# ADS1274.net
KiCad netlist of a schematic drawn in Altium Designer
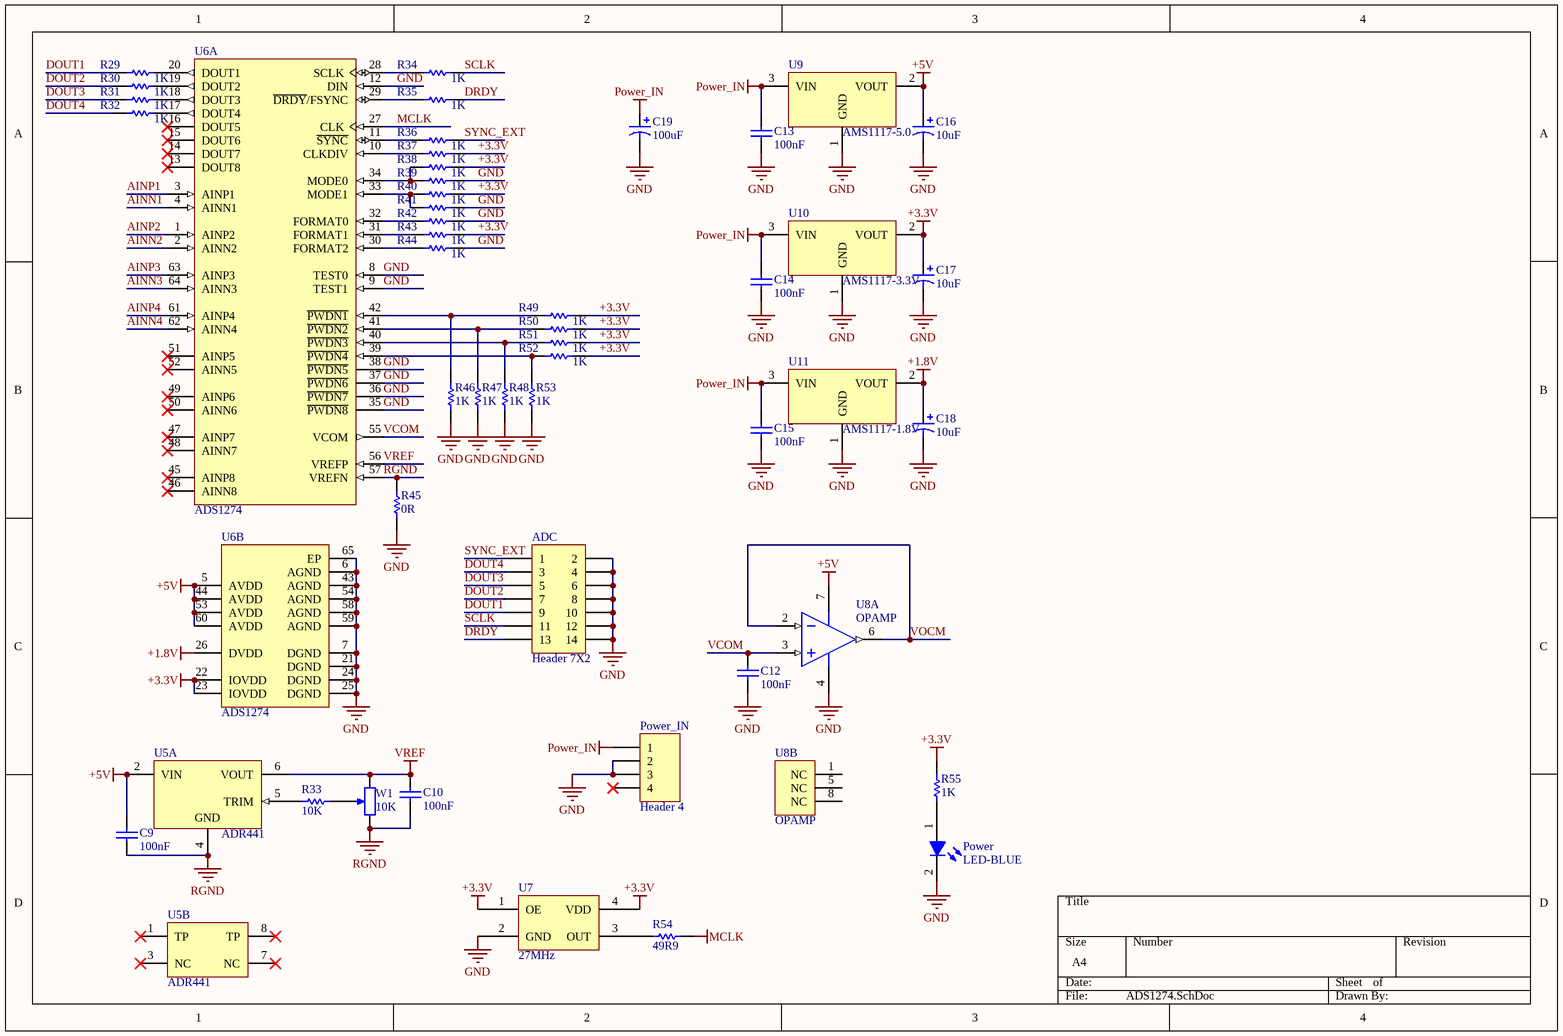
[diagram p0: ADS1274.SchDoc]

(export (version "E")
  (design (tool "Eeschema 10.0.6"))
  (components
    (comp (ref "ADC")
      (value "Header 7X2")
      (footprint "HEADER7X2")
      (description "Header, 7-Pin, Dual row")
      (fields (field (name "PUBLISHER") "Altium Limited"))
      (libsource (lib "Miscellaneous Connectors") (part "Header 7X2"))
    )
    (comp (ref "C9")
      (value "100nF")
      (footprint "CAPC0603(1608)55_M")
      (libsource (lib "Slivy's ibrary") (part "CAP"))
    )
    (comp (ref "C10")
      (value "100nF")
      (footprint "CAPC0603(1608)55_M")
      (libsource (lib "Slivy's ibrary") (part "CAP"))
    )
    (comp (ref "C12")
      (value "100nF")
      (footprint "CAPC0603(1608)55_M")
      (libsource (lib "Slivy's ibrary") (part "CAP"))
    )
    (comp (ref "C13")
      (value "100nF")
      (footprint "CAPC0603(1608)55_M")
      (libsource (lib "Slivy's ibrary") (part "CAP"))
    )
    (comp (ref "C14")
      (value "100nF")
      (footprint "CAPC0603(1608)55_M")
      (libsource (lib "Slivy's ibrary") (part "CAP"))
    )
    (comp (ref "C15")
      (value "100nF")
      (footprint "CAPC0603(1608)55_M")
      (libsource (lib "Slivy's ibrary") (part "CAP"))
    )
    (comp (ref "C16")
      (value "10uF")
      (footprint "CAPC3528")
      (libsource (lib "Slivy's ibrary") (part "CAP-Pol"))
    )
    (comp (ref "C17")
      (value "10uF")
      (footprint "CAPC3528")
      (libsource (lib "Slivy's ibrary") (part "CAP-Pol"))
    )
    (comp (ref "C18")
      (value "10uF")
      (footprint "CAPC3528")
      (libsource (lib "Slivy's ibrary") (part "CAP-Pol"))
    )
    (comp (ref "C19")
      (value "100uF")
      (footprint "CAPC7343")
      (libsource (lib "Slivy's ibrary") (part "CAP-Pol"))
    )
    (comp (ref "Power")
      (value "LED-BLUE")
      (footprint "0603LED_BLUE_V")
      (libsource (lib "Slivy's ibrary") (part "LED-BLUE"))
    )
    (comp (ref "Power_IN")
      (value "Header 4")
      (footprint "3.96-4")
      (description "Header, 4-Pin")
      (fields (field (name "PUBLISHER") "Altium Limited"))
      (libsource (lib "Miscellaneous Connectors") (part "Header 4"))
    )
    (comp (ref "R29")
      (value "1K")
      (footprint "RESC0603(1608)_M")
      (libsource (lib "Slivy's ibrary") (part "RES"))
    )
    (comp (ref "R30")
      (value "1K")
      (footprint "RESC0603(1608)_M")
      (libsource (lib "Slivy's ibrary") (part "RES"))
    )
    (comp (ref "R31")
      (value "1K")
      (footprint "RESC0603(1608)_M")
      (libsource (lib "Slivy's ibrary") (part "RES"))
    )
    (comp (ref "R32")
      (value "1K")
      (footprint "RESC0603(1608)_M")
      (libsource (lib "Slivy's ibrary") (part "RES"))
    )
    (comp (ref "R33")
      (value "10K")
      (footprint "RESC0603(1608)_M")
      (libsource (lib "Slivy's ibrary") (part "RES"))
    )
    (comp (ref "R34")
      (value "1K")
      (footprint "RESC0603(1608)_M")
      (libsource (lib "Slivy's ibrary") (part "RES"))
    )
    (comp (ref "R35")
      (value "1K")
      (footprint "RESC0603(1608)_M")
      (libsource (lib "Slivy's ibrary") (part "RES"))
    )
    (comp (ref "R36")
      (value "1K")
      (footprint "RESC0603(1608)_M")
      (libsource (lib "Slivy's ibrary") (part "RES"))
    )
    (comp (ref "R37")
      (value "1K")
      (footprint "RESC0603(1608)_M")
      (libsource (lib "Slivy's ibrary") (part "RES"))
    )
    (comp (ref "R38")
      (value "1K")
      (footprint "RESC0603(1608)_M")
      (libsource (lib "Slivy's ibrary") (part "RES"))
    )
    (comp (ref "R39")
      (value "1K")
      (footprint "RESC0603(1608)_M")
      (libsource (lib "Slivy's ibrary") (part "RES"))
    )
    (comp (ref "R40")
      (value "1K")
      (footprint "RESC0603(1608)_M")
      (libsource (lib "Slivy's ibrary") (part "RES"))
    )
    (comp (ref "R41")
      (value "1K")
      (footprint "RESC0603(1608)_M")
      (libsource (lib "Slivy's ibrary") (part "RES"))
    )
    (comp (ref "R42")
      (value "1K")
      (footprint "RESC0603(1608)_M")
      (libsource (lib "Slivy's ibrary") (part "RES"))
    )
    (comp (ref "R43")
      (value "1K")
      (footprint "RESC0603(1608)_M")
      (libsource (lib "Slivy's ibrary") (part "RES"))
    )
    (comp (ref "R44")
      (value "1K")
      (footprint "RESC0603(1608)_M")
      (libsource (lib "Slivy's ibrary") (part "RES"))
    )
    (comp (ref "R45")
      (value "0R")
      (footprint "RESC0603(1608)_M")
      (libsource (lib "Slivy's ibrary") (part "RES"))
    )
    (comp (ref "R46")
      (value "1K")
      (footprint "RESC0603(1608)_M")
      (libsource (lib "Slivy's ibrary") (part "RES"))
    )
    (comp (ref "R47")
      (value "1K")
      (footprint "RESC0603(1608)_M")
      (libsource (lib "Slivy's ibrary") (part "RES"))
    )
    (comp (ref "R48")
      (value "1K")
      (footprint "RESC0603(1608)_M")
      (libsource (lib "Slivy's ibrary") (part "RES"))
    )
    (comp (ref "R49")
      (value "1K")
      (footprint "RESC0603(1608)_M")
      (libsource (lib "Slivy's ibrary") (part "RES"))
    )
    (comp (ref "R50")
      (value "1K")
      (footprint "RESC0603(1608)_M")
      (libsource (lib "Slivy's ibrary") (part "RES"))
    )
    (comp (ref "R51")
      (value "1K")
      (footprint "RESC0603(1608)_M")
      (libsource (lib "Slivy's ibrary") (part "RES"))
    )
    (comp (ref "R52")
      (value "1K")
      (footprint "RESC0603(1608)_M")
      (libsource (lib "Slivy's ibrary") (part "RES"))
    )
    (comp (ref "R53")
      (value "1K")
      (footprint "RESC0603(1608)_M")
      (libsource (lib "Slivy's ibrary") (part "RES"))
    )
    (comp (ref "R54")
      (value "49R9")
      (footprint "RESC0603(1608)_M")
      (libsource (lib "Slivy's ibrary") (part "RES"))
    )
    (comp (ref "R55")
      (value "1K")
      (footprint "RESC0603(1608)_M")
      (libsource (lib "Slivy's ibrary") (part "RES"))
    )
    (comp (ref "U5") (value "ADR441") (footprint "SOIC8") (libsource (lib "Slivy's ibrary") (part "ADR421")))
    (comp (ref "U6") (value "ADS1274") (footprint "EQFP64") (libsource (lib "") (part "ADS1274_1")))
    (comp (ref "U7")
      (value "27MHz")
      (footprint "SMD7050")
      (libsource (lib "Integrated_Library1") (part "OSC7050"))
    )
    (comp (ref "U8") (value "OPAMP") (footprint "SOIC8") (libsource (lib "Slivy's ibrary") (part "OPAMP")))
    (comp (ref "U9")
      (value "AMS1117-5.0")
      (footprint "SOT-223_M")
      (libsource (lib "Slivy's ibrary") (part "AMS1117"))
    )
    (comp (ref "U10")
      (value "AMS1117-3.3V")
      (footprint "SOT-223_M")
      (libsource (lib "Slivy's ibrary") (part "AMS1117"))
    )
    (comp (ref "U11")
      (value "AMS1117-1.8V")
      (footprint "SOT-223_M")
      (libsource (lib "Slivy's ibrary") (part "AMS1117"))
    )
    (comp (ref "W1")
      (value "10K")
      (footprint "VR5")
      (description "Potentiometer")
      (fields
        (field (name "MANUFACTURER") "Generic Components")
        (field (name "PUBLISHER") "Altium Hobart Technology Centre")
      )
      (libsource (lib "Integrated_Library1") (part "RPot2"))
    )
  )
  (nets
    (net (code "1") (name "+1.8V") (class "Default")
      (node (ref "C18") (pin "1") (pinfunction "1_1") (pintype "passive"))
      (node (ref "U11") (pin "2") (pinfunction "VOUT_2") (pintype "power_in"))
      (node (ref "U6") (pin "26") (pinfunction "DVDD_26") (pintype "power_in"))
    )
    (net (code "2") (name "+3.3V") (class "Default")
      (node (ref "C17") (pin "1") (pinfunction "1_1") (pintype "passive"))
      (node (ref "R37") (pin "2") (pinfunction "2_2") (pintype "passive"))
      (node (ref "R38") (pin "2") (pinfunction "2_2") (pintype "passive"))
      (node (ref "R40") (pin "2") (pinfunction "2_2") (pintype "passive"))
      (node (ref "R43") (pin "2") (pinfunction "2_2") (pintype "passive"))
      (node (ref "R49") (pin "2") (pinfunction "2_2") (pintype "passive"))
      (node (ref "R50") (pin "2") (pinfunction "2_2") (pintype "passive"))
      (node (ref "R51") (pin "2") (pinfunction "2_2") (pintype "passive"))
      (node (ref "R52") (pin "2") (pinfunction "2_2") (pintype "passive"))
      (node (ref "R55") (pin "2") (pinfunction "2_2") (pintype "passive"))
      (node (ref "U10") (pin "2") (pinfunction "VOUT_2") (pintype "power_in"))
      (node (ref "U6") (pin "22") (pinfunction "IOVDD_22") (pintype "power_in"))
      (node (ref "U6") (pin "23") (pinfunction "IOVDD_23") (pintype "power_in"))
      (node (ref "U7") (pin "1") (pinfunction "OE_1") (pintype "passive"))
      (node (ref "U7") (pin "4") (pinfunction "VDD_4") (pintype "passive"))
    )
    (net (code "3") (name "+5V") (class "Default")
      (node (ref "C16") (pin "1") (pinfunction "1_1") (pintype "passive"))
      (node (ref "C9") (pin "2") (pinfunction "2_2") (pintype "passive"))
      (node (ref "U5") (pin "2") (pinfunction "VIN_2") (pintype "power_in"))
      (node (ref "U6") (pin "44") (pinfunction "AVDD_44") (pintype "power_in"))
      (node (ref "U6") (pin "5") (pinfunction "AVDD_5") (pintype "power_in"))
      (node (ref "U6") (pin "53") (pinfunction "AVDD_53") (pintype "power_in"))
      (node (ref "U6") (pin "60") (pinfunction "AVDD_60") (pintype "power_in"))
      (node (ref "U8") (pin "7") (pinfunction "V+_7") (pintype "power_in"))
      (node (ref "U9") (pin "2") (pinfunction "VOUT_2") (pintype "power_in"))
    )
    (net (code "4") (name "/AINN1") (class "Default")
      (node (ref "U6") (pin "4") (pinfunction "AINN1_4") (pintype "input"))
    )
    (net (code "5") (name "/AINN2") (class "Default")
      (node (ref "U6") (pin "2") (pinfunction "AINN2_2") (pintype "input"))
    )
    (net (code "6") (name "/AINN3") (class "Default")
      (node (ref "U6") (pin "64") (pinfunction "AINN3_64") (pintype "input"))
    )
    (net (code "7") (name "/AINN4") (class "Default")
      (node (ref "U6") (pin "62") (pinfunction "AINN4_62") (pintype "input"))
    )
    (net (code "8") (name "/AINP1") (class "Default")
      (node (ref "U6") (pin "3") (pinfunction "AINP1_3") (pintype "input"))
    )
    (net (code "9") (name "/AINP2") (class "Default")
      (node (ref "U6") (pin "1") (pinfunction "AINP2_1") (pintype "input"))
    )
    (net (code "10") (name "/AINP3") (class "Default")
      (node (ref "U6") (pin "63") (pinfunction "AINP3_63") (pintype "input"))
    )
    (net (code "11") (name "/AINP4") (class "Default")
      (node (ref "U6") (pin "61") (pinfunction "AINP4_61") (pintype "input"))
    )
    (net (code "12") (name "/DOUT1") (class "Default")
      (node (ref "ADC") (pin "9") (pinfunction "9_9") (pintype "passive"))
      (node (ref "R29") (pin "1") (pinfunction "1_1") (pintype "passive"))
    )
    (net (code "13") (name "/DOUT2") (class "Default")
      (node (ref "ADC") (pin "7") (pinfunction "7_7") (pintype "passive"))
      (node (ref "R30") (pin "1") (pinfunction "1_1") (pintype "passive"))
    )
    (net (code "14") (name "/DOUT3") (class "Default")
      (node (ref "ADC") (pin "5") (pinfunction "5_5") (pintype "passive"))
      (node (ref "R31") (pin "1") (pinfunction "1_1") (pintype "passive"))
    )
    (net (code "15") (name "/DOUT4") (class "Default")
      (node (ref "ADC") (pin "3") (pinfunction "3_3") (pintype "passive"))
      (node (ref "R32") (pin "1") (pinfunction "1_1") (pintype "passive"))
    )
    (net (code "16") (name "/DRDY") (class "Default")
      (node (ref "ADC") (pin "13") (pinfunction "13_13") (pintype "passive"))
      (node (ref "R35") (pin "2") (pinfunction "2_2") (pintype "passive"))
    )
    (net (code "17") (name "/SCLK") (class "Default")
      (node (ref "ADC") (pin "11") (pinfunction "11_11") (pintype "passive"))
      (node (ref "R34") (pin "2") (pinfunction "2_2") (pintype "passive"))
    )
    (net (code "18") (name "/SYNC_EXT") (class "Default")
      (node (ref "ADC") (pin "1") (pinfunction "1_1") (pintype "passive"))
      (node (ref "R36") (pin "2") (pinfunction "2_2") (pintype "passive"))
    )
    (net (code "19") (name "/VCOM") (class "Default")
      (node (ref "C12") (pin "2") (pinfunction "2_2") (pintype "passive"))
      (node (ref "U6") (pin "55") (pinfunction "VCOM_55") (pintype "output"))
      (node (ref "U8") (pin "3") (pinfunction "IN+_3") (pintype "input"))
    )
    (net (code "20") (name "/VOCM") (class "Default")
      (node (ref "U8") (pin "2") (pinfunction "IN-_2") (pintype "input"))
      (node (ref "U8") (pin "6") (pinfunction "OUT_6") (pintype "output"))
    )
    (net (code "21") (name "GND") (class "Default")
      (node (ref "ADC") (pin "10") (pinfunction "10_10") (pintype "passive"))
      (node (ref "ADC") (pin "12") (pinfunction "12_12") (pintype "passive"))
      (node (ref "ADC") (pin "14") (pinfunction "14_14") (pintype "passive"))
      (node (ref "ADC") (pin "2") (pinfunction "2_2") (pintype "passive"))
      (node (ref "ADC") (pin "4") (pinfunction "4_4") (pintype "passive"))
      (node (ref "ADC") (pin "6") (pinfunction "6_6") (pintype "passive"))
      (node (ref "ADC") (pin "8") (pinfunction "8_8") (pintype "passive"))
      (node (ref "C12") (pin "1") (pinfunction "1_1") (pintype "passive"))
      (node (ref "C13") (pin "1") (pinfunction "1_1") (pintype "passive"))
      (node (ref "C14") (pin "1") (pinfunction "1_1") (pintype "passive"))
      (node (ref "C15") (pin "1") (pinfunction "1_1") (pintype "passive"))
      (node (ref "C16") (pin "2") (pinfunction "2_2") (pintype "passive"))
      (node (ref "C17") (pin "2") (pinfunction "2_2") (pintype "passive"))
      (node (ref "C18") (pin "2") (pinfunction "2_2") (pintype "passive"))
      (node (ref "C19") (pin "2") (pinfunction "2_2") (pintype "passive"))
      (node (ref "Power") (pin "2") (pinfunction "K_2") (pintype "passive"))
      (node (ref "Power_IN") (pin "2") (pinfunction "2_2") (pintype "passive"))
      (node (ref "Power_IN") (pin "3") (pinfunction "3_3") (pintype "passive"))
      (node (ref "R39") (pin "2") (pinfunction "2_2") (pintype "passive"))
      (node (ref "R41") (pin "2") (pinfunction "2_2") (pintype "passive"))
      (node (ref "R42") (pin "2") (pinfunction "2_2") (pintype "passive"))
      (node (ref "R44") (pin "2") (pinfunction "2_2") (pintype "passive"))
      (node (ref "R45") (pin "1") (pinfunction "1_1") (pintype "passive"))
      (node (ref "R46") (pin "1") (pinfunction "1_1") (pintype "passive"))
      (node (ref "R47") (pin "1") (pinfunction "1_1") (pintype "passive"))
      (node (ref "R48") (pin "1") (pinfunction "1_1") (pintype "passive"))
      (node (ref "R53") (pin "1") (pinfunction "1_1") (pintype "passive"))
      (node (ref "U10") (pin "1") (pinfunction "GND_1") (pintype "power_in"))
      (node (ref "U11") (pin "1") (pinfunction "GND_1") (pintype "power_in"))
      (node (ref "U6") (pin "12") (pinfunction "DIN_12") (pintype "input"))
      (node (ref "U6") (pin "21") (pinfunction "DGND_21") (pintype "power_in"))
      (node (ref "U6") (pin "24") (pinfunction "DGND_24") (pintype "power_in"))
      (node (ref "U6") (pin "25") (pinfunction "DGND_25") (pintype "power_in"))
      (node (ref "U6") (pin "35") (pinfunction "~{PWDN8}_35") (pintype "passive"))
      (node (ref "U6") (pin "36") (pinfunction "~{PWDN7}_36") (pintype "passive"))
      (node (ref "U6") (pin "37") (pinfunction "~{PWDN6}_37") (pintype "passive"))
      (node (ref "U6") (pin "38") (pinfunction "~{PWDN5}_38") (pintype "passive"))
      (node (ref "U6") (pin "43") (pinfunction "AGND_43") (pintype "power_in"))
      (node (ref "U6") (pin "54") (pinfunction "AGND_54") (pintype "power_in"))
      (node (ref "U6") (pin "58") (pinfunction "AGND_58") (pintype "power_in"))
      (node (ref "U6") (pin "59") (pinfunction "AGND_59") (pintype "power_in"))
      (node (ref "U6") (pin "6") (pinfunction "AGND_6") (pintype "power_in"))
      (node (ref "U6") (pin "65") (pinfunction "EP_65") (pintype "passive"))
      (node (ref "U6") (pin "7") (pinfunction "DGND_7") (pintype "power_in"))
      (node (ref "U6") (pin "8") (pinfunction "TEST0_8") (pintype "input"))
      (node (ref "U6") (pin "9") (pinfunction "TEST1_9") (pintype "input"))
      (node (ref "U7") (pin "2") (pinfunction "GND_2") (pintype "passive"))
      (node (ref "U8") (pin "4") (pinfunction "V-_4") (pintype "power_in"))
      (node (ref "U9") (pin "1") (pinfunction "GND_1") (pintype "power_in"))
    )
    (net (code "22") (name "MCLK") (class "Default")
      (node (ref "R54") (pin "2") (pinfunction "2_2") (pintype "passive"))
      (node (ref "U6") (pin "27") (pinfunction "CLK_27") (pintype "input"))
    )
    (net (code "23") (name "Net-(Power-A)") (class "Default")
      (node (ref "Power") (pin "1") (pinfunction "A_1") (pintype "passive"))
      (node (ref "R55") (pin "1") (pinfunction "1_1") (pintype "passive"))
    )
    (net (code "24") (name "Net-(U5A-TRIM)") (class "Default")
      (node (ref "R33") (pin "1") (pinfunction "1_1") (pintype "passive"))
      (node (ref "U5") (pin "5") (pinfunction "TRIM_5") (pintype "input"))
    )
    (net (code "25") (name "Net-(U6A-CLKDIV)") (class "Default")
      (node (ref "R37") (pin "1") (pinfunction "1_1") (pintype "passive"))
      (node (ref "U6") (pin "10") (pinfunction "CLKDIV_10") (pintype "input"))
    )
    (net (code "26") (name "Net-(U6A-DOUT1)") (class "Default")
      (node (ref "R29") (pin "2") (pinfunction "2_2") (pintype "passive"))
      (node (ref "U6") (pin "20") (pinfunction "DOUT1_20") (pintype "output"))
    )
    (net (code "27") (name "Net-(U6A-DOUT2)") (class "Default")
      (node (ref "R30") (pin "2") (pinfunction "2_2") (pintype "passive"))
      (node (ref "U6") (pin "19") (pinfunction "DOUT2_19") (pintype "output"))
    )
    (net (code "28") (name "Net-(U6A-DOUT3)") (class "Default")
      (node (ref "R31") (pin "2") (pinfunction "2_2") (pintype "passive"))
      (node (ref "U6") (pin "18") (pinfunction "DOUT3_18") (pintype "output"))
    )
    (net (code "29") (name "Net-(U6A-DOUT4)") (class "Default")
      (node (ref "R32") (pin "2") (pinfunction "2_2") (pintype "passive"))
      (node (ref "U6") (pin "17") (pinfunction "DOUT4_17") (pintype "output"))
    )
    (net (code "30") (name "Net-(U6A-FORMAT0)") (class "Default")
      (node (ref "R42") (pin "1") (pinfunction "1_1") (pintype "passive"))
      (node (ref "U6") (pin "32") (pinfunction "FORMAT0_32") (pintype "input"))
    )
    (net (code "31") (name "Net-(U6A-FORMAT1)") (class "Default")
      (node (ref "R43") (pin "1") (pinfunction "1_1") (pintype "passive"))
      (node (ref "U6") (pin "31") (pinfunction "FORMAT1_31") (pintype "input"))
    )
    (net (code "32") (name "Net-(U6A-FORMAT2)") (class "Default")
      (node (ref "R44") (pin "1") (pinfunction "1_1") (pintype "passive"))
      (node (ref "U6") (pin "30") (pinfunction "FORMAT2_30") (pintype "input"))
    )
    (net (code "33") (name "Net-(U6A-MODE0)") (class "Default")
      (node (ref "R38") (pin "1") (pinfunction "1_1") (pintype "passive"))
      (node (ref "R39") (pin "1") (pinfunction "1_1") (pintype "passive"))
      (node (ref "U6") (pin "34") (pinfunction "MODE0_34") (pintype "input"))
    )
    (net (code "34") (name "Net-(U6A-MODE1)") (class "Default")
      (node (ref "R40") (pin "1") (pinfunction "1_1") (pintype "passive"))
      (node (ref "R41") (pin "1") (pinfunction "1_1") (pintype "passive"))
      (node (ref "U6") (pin "33") (pinfunction "MODE1_33") (pintype "input"))
    )
    (net (code "35") (name "Net-(U6A-SCLK)") (class "Default")
      (node (ref "R34") (pin "1") (pinfunction "1_1") (pintype "passive"))
      (node (ref "U6") (pin "28") (pinfunction "SCLK_28") (pintype "bidirectional"))
    )
    (net (code "36") (name "Net-(U6A-~{DRDY}{slash}FSYNC)") (class "Default")
      (node (ref "R35") (pin "1") (pinfunction "1_1") (pintype "passive"))
      (node (ref "U6") (pin "29") (pinfunction "~{DRDY}/FSYNC_29") (pintype "bidirectional"))
    )
    (net (code "37") (name "Net-(U6A-~{PWDN1})") (class "Default")
      (node (ref "R46") (pin "2") (pinfunction "2_2") (pintype "passive"))
      (node (ref "R49") (pin "1") (pinfunction "1_1") (pintype "passive"))
      (node (ref "U6") (pin "42") (pinfunction "~{PWDN1}_42") (pintype "input"))
    )
    (net (code "38") (name "Net-(U6A-~{PWDN2})") (class "Default")
      (node (ref "R47") (pin "2") (pinfunction "2_2") (pintype "passive"))
      (node (ref "R50") (pin "1") (pinfunction "1_1") (pintype "passive"))
      (node (ref "U6") (pin "41") (pinfunction "~{PWDN2}_41") (pintype "input"))
    )
    (net (code "39") (name "Net-(U6A-~{PWDN3})") (class "Default")
      (node (ref "R48") (pin "2") (pinfunction "2_2") (pintype "passive"))
      (node (ref "R51") (pin "1") (pinfunction "1_1") (pintype "passive"))
      (node (ref "U6") (pin "40") (pinfunction "~{PWDN3}_40") (pintype "input"))
    )
    (net (code "40") (name "Net-(U6A-~{PWDN4})") (class "Default")
      (node (ref "R52") (pin "1") (pinfunction "1_1") (pintype "passive"))
      (node (ref "R53") (pin "2") (pinfunction "2_2") (pintype "passive"))
      (node (ref "U6") (pin "39") (pinfunction "~{PWDN4}_39") (pintype "input"))
    )
    (net (code "41") (name "Net-(U6A-~{SYNC})") (class "Default")
      (node (ref "R36") (pin "1") (pinfunction "1_1") (pintype "passive"))
      (node (ref "U6") (pin "11") (pinfunction "~{SYNC}_11") (pintype "bidirectional"))
    )
    (net (code "42") (name "Net-(U7-OUT)") (class "Default")
      (node (ref "R54") (pin "1") (pinfunction "1_1") (pintype "passive"))
      (node (ref "U7") (pin "3") (pinfunction "OUT_3") (pintype "passive"))
    )
    (net (code "43") (name "Net-(W1-TAP)") (class "Default")
      (node (ref "R33") (pin "2") (pinfunction "2_2") (pintype "passive"))
      (node (ref "W1") (pin "2") (pinfunction "TAP_2") (pintype "passive"))
    )
    (net (code "44") (name "Power_IN") (class "Default")
      (node (ref "C13") (pin "2") (pinfunction "2_2") (pintype "passive"))
      (node (ref "C14") (pin "2") (pinfunction "2_2") (pintype "passive"))
      (node (ref "C15") (pin "2") (pinfunction "2_2") (pintype "passive"))
      (node (ref "C19") (pin "1") (pinfunction "1_1") (pintype "passive"))
      (node (ref "Power_IN") (pin "1") (pinfunction "1_1") (pintype "passive"))
      (node (ref "U10") (pin "3") (pinfunction "VIN_3") (pintype "power_in"))
      (node (ref "U11") (pin "3") (pinfunction "VIN_3") (pintype "power_in"))
      (node (ref "U9") (pin "3") (pinfunction "VIN_3") (pintype "power_in"))
    )
    (net (code "45") (name "RGND") (class "Default")
      (node (ref "C10") (pin "1") (pinfunction "1_1") (pintype "passive"))
      (node (ref "C9") (pin "1") (pinfunction "1_1") (pintype "passive"))
      (node (ref "R45") (pin "2") (pinfunction "2_2") (pintype "passive"))
      (node (ref "U5") (pin "4") (pinfunction "GND_4") (pintype "power_in"))
      (node (ref "U6") (pin "57") (pinfunction "VREFN_57") (pintype "input"))
      (node (ref "W1") (pin "3") (pinfunction "BOT_3") (pintype "passive"))
    )
    (net (code "46") (name "VREF") (class "Default")
      (node (ref "C10") (pin "2") (pinfunction "2_2") (pintype "passive"))
      (node (ref "U5") (pin "6") (pinfunction "VOUT_6") (pintype "power_in"))
      (node (ref "U6") (pin "56") (pinfunction "VREFP_56") (pintype "input"))
      (node (ref "W1") (pin "1") (pinfunction "TOP_1") (pintype "passive"))
    )
    (net (code "47") (name "unconnected-(Power_IN-Pad4)") (class "Default")
      (node (ref "Power_IN") (pin "4") (pinfunction "4_4") (pintype "passive+no_connect"))
    )
    (net (code "48") (name "unconnected-(U5B-NC-Pad3)") (class "Default")
      (node (ref "U5") (pin "3") (pinfunction "NC_3") (pintype "passive+no_connect"))
    )
    (net (code "49") (name "unconnected-(U5B-NC-Pad7)") (class "Default")
      (node (ref "U5") (pin "7") (pinfunction "NC_7") (pintype "passive+no_connect"))
    )
    (net (code "50") (name "unconnected-(U5B-TP-Pad1)") (class "Default")
      (node (ref "U5") (pin "1") (pinfunction "TP_1") (pintype "passive+no_connect"))
    )
    (net (code "51") (name "unconnected-(U5B-TP-Pad8)") (class "Default")
      (node (ref "U5") (pin "8") (pinfunction "TP_8") (pintype "passive+no_connect"))
    )
    (net (code "52") (name "unconnected-(U6A-AINN5-Pad52)") (class "Default")
      (node (ref "U6") (pin "52") (pinfunction "AINN5_52") (pintype "passive+no_connect"))
    )
    (net (code "53") (name "unconnected-(U6A-AINN6-Pad50)") (class "Default")
      (node (ref "U6") (pin "50") (pinfunction "AINN6_50") (pintype "passive+no_connect"))
    )
    (net (code "54") (name "unconnected-(U6A-AINN7-Pad48)") (class "Default")
      (node (ref "U6") (pin "48") (pinfunction "AINN7_48") (pintype "passive+no_connect"))
    )
    (net (code "55") (name "unconnected-(U6A-AINN8-Pad46)") (class "Default")
      (node (ref "U6") (pin "46") (pinfunction "AINN8_46") (pintype "passive+no_connect"))
    )
    (net (code "56") (name "unconnected-(U6A-AINP5-Pad51)") (class "Default")
      (node (ref "U6") (pin "51") (pinfunction "AINP5_51") (pintype "passive+no_connect"))
    )
    (net (code "57") (name "unconnected-(U6A-AINP6-Pad49)") (class "Default")
      (node (ref "U6") (pin "49") (pinfunction "AINP6_49") (pintype "passive+no_connect"))
    )
    (net (code "58") (name "unconnected-(U6A-AINP7-Pad47)") (class "Default")
      (node (ref "U6") (pin "47") (pinfunction "AINP7_47") (pintype "passive+no_connect"))
    )
    (net (code "59") (name "unconnected-(U6A-AINP8-Pad45)") (class "Default")
      (node (ref "U6") (pin "45") (pinfunction "AINP8_45") (pintype "passive+no_connect"))
    )
    (net (code "60") (name "unconnected-(U6A-DOUT5-Pad16)") (class "Default")
      (node (ref "U6") (pin "16") (pinfunction "DOUT5_16") (pintype "passive+no_connect"))
    )
    (net (code "61") (name "unconnected-(U6A-DOUT6-Pad15)") (class "Default")
      (node (ref "U6") (pin "15") (pinfunction "DOUT6_15") (pintype "passive+no_connect"))
    )
    (net (code "62") (name "unconnected-(U6A-DOUT7-Pad14)") (class "Default")
      (node (ref "U6") (pin "14") (pinfunction "DOUT7_14") (pintype "passive+no_connect"))
    )
    (net (code "63") (name "unconnected-(U6A-DOUT8-Pad13)") (class "Default")
      (node (ref "U6") (pin "13") (pinfunction "DOUT8_13") (pintype "passive+no_connect"))
    )
    (net (code "64") (name "unconnected-(U8B-NC-Pad1)") (class "Default")
      (node (ref "U8") (pin "1") (pinfunction "NC_1") (pintype "passive"))
    )
    (net (code "65") (name "unconnected-(U8B-NC-Pad5)") (class "Default")
      (node (ref "U8") (pin "5") (pinfunction "NC_5") (pintype "passive"))
    )
    (net (code "66") (name "unconnected-(U8B-NC-Pad8)") (class "Default")
      (node (ref "U8") (pin "8") (pinfunction "NC_8") (pintype "passive"))
    )
  )
)
